# SA612Mixer_Simple.net
KiCad netlist of a schematic drawn in EAGLE
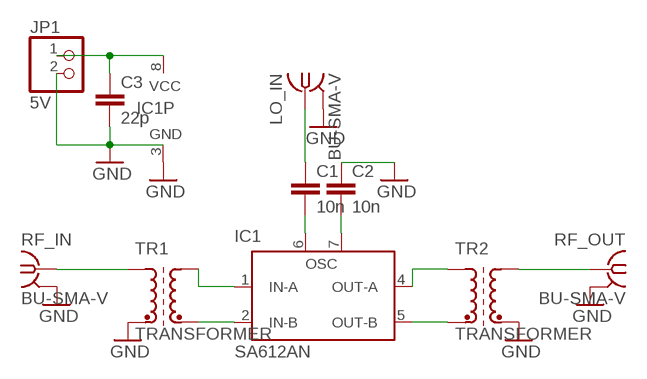
[diagram p0: schematic, sheet 1]

(export (version "E")
  (design (tool "Eeschema 10.0.6"))
  (components
    (comp (ref "C1")
      (value "10n")
      (footprint "eagle-import:C5B2.5")
      (libsource (lib "eagle-import") (part "C5/2.5"))
    )
    (comp (ref "C2")
      (value "10n")
      (footprint "eagle-import:C5B2.5")
      (libsource (lib "eagle-import") (part "C5/2.5"))
    )
    (comp (ref "C3")
      (value "22p")
      (footprint "eagle-import:C5B2.5")
      (libsource (lib "eagle-import") (part "C5/2.5"))
    )
    (comp (ref "IC1")
      (value "SA612AN")
      (footprint "eagle-import:DIL08")
      (libsource (lib "eagle-import") (part "SA612AN"))
    )
    (comp (ref "JP1")
      (value "5V")
      (footprint "eagle-import:1X02")
      (libsource (lib "eagle-import") (part "PINHD-1X2"))
    )
    (comp (ref "LO_IN")
      (value "BU-SMA-V")
      (footprint "eagle-import:BU-SMA-V")
      (libsource (lib "eagle-import") (part "BU-SMA-V"))
    )
    (comp (ref "RF_IN")
      (value "BU-SMA-V")
      (footprint "eagle-import:BU-SMA-V")
      (libsource (lib "eagle-import") (part "BU-SMA-V"))
    )
    (comp (ref "RF_OUT")
      (value "BU-SMA-V")
      (footprint "eagle-import:BU-SMA-V")
      (libsource (lib "eagle-import") (part "BU-SMA-V"))
    )
    (comp (ref "TR1")
      (value "TRANSFORMER")
      (footprint "eagle-import:TRANSFORMER1")
      (libsource (lib "eagle-import") (part "TRANSFORMER"))
    )
    (comp (ref "TR2")
      (value "TRANSFORMER")
      (footprint "eagle-import:TRANSFORMER1")
      (libsource (lib "eagle-import") (part "TRANSFORMER"))
    )
  )
  (nets
    (net (code "1") (name "GND") (class "Default")
      (node (ref "C2") (pin "1") (pinfunction "1_1") (pintype "passive"))
      (node (ref "C3") (pin "2") (pinfunction "2_2") (pintype "passive"))
      (node (ref "IC1") (pin "3") (pinfunction "GND_3") (pintype "power_in"))
      (node (ref "JP1") (pin "2") (pinfunction "2_2") (pintype "passive"))
      (node (ref "LO_IN") (pin "2") (pinfunction "2_2") (pintype "passive"))
      (node (ref "LO_IN") (pin "3") (pinfunction "2_3") (pintype "passive"))
      (node (ref "LO_IN") (pin "4") (pinfunction "2_4") (pintype "passive"))
      (node (ref "LO_IN") (pin "5") (pinfunction "2_5") (pintype "passive"))
      (node (ref "RF_IN") (pin "2") (pinfunction "2_2") (pintype "passive"))
      (node (ref "RF_IN") (pin "3") (pinfunction "2_3") (pintype "passive"))
      (node (ref "RF_IN") (pin "4") (pinfunction "2_4") (pintype "passive"))
      (node (ref "RF_IN") (pin "5") (pinfunction "2_5") (pintype "passive"))
      (node (ref "RF_OUT") (pin "2") (pinfunction "2_2") (pintype "passive"))
      (node (ref "RF_OUT") (pin "3") (pinfunction "2_3") (pintype "passive"))
      (node (ref "RF_OUT") (pin "4") (pinfunction "2_4") (pintype "passive"))
      (node (ref "RF_OUT") (pin "5") (pinfunction "2_5") (pintype "passive"))
      (node (ref "TR1") (pin "P$2") (pinfunction "E1_P$2") (pintype "passive"))
      (node (ref "TR2") (pin "P$4") (pinfunction "E2_P$4") (pintype "passive"))
    )
    (net (code "2") (name "Net-(C1-Pad1)") (class "Default")
      (node (ref "C1") (pin "1") (pinfunction "1_1") (pintype "passive"))
      (node (ref "LO_IN") (pin "1") (pinfunction "1_1") (pintype "passive"))
    )
    (net (code "3") (name "Net-(IC1A-IN-A)") (class "Default")
      (node (ref "IC1") (pin "1") (pinfunction "IN-A_1") (pintype "input"))
      (node (ref "TR1") (pin "P$3") (pinfunction "A2_P$3") (pintype "passive"))
    )
    (net (code "4") (name "Net-(IC1A-IN-B)") (class "Default")
      (node (ref "IC1") (pin "2") (pinfunction "IN-B_2") (pintype "input"))
      (node (ref "TR1") (pin "P$4") (pinfunction "E2_P$4") (pintype "passive"))
    )
    (net (code "5") (name "Net-(IC1A-OSC')") (class "Default")
      (node (ref "C2") (pin "2") (pinfunction "2_2") (pintype "passive"))
      (node (ref "IC1") (pin "7") (pinfunction "OSC'_7") (pintype "passive"))
    )
    (net (code "6") (name "Net-(IC1A-OSC)") (class "Default")
      (node (ref "C1") (pin "2") (pinfunction "2_2") (pintype "passive"))
      (node (ref "IC1") (pin "6") (pinfunction "OSC_6") (pintype "passive"))
    )
    (net (code "7") (name "Net-(IC1A-OUT-A)") (class "Default")
      (node (ref "IC1") (pin "4") (pinfunction "OUT-A_4") (pintype "input"))
      (node (ref "TR2") (pin "P$1") (pinfunction "A1_P$1") (pintype "passive"))
    )
    (net (code "8") (name "Net-(IC1A-OUT-B)") (class "Default")
      (node (ref "IC1") (pin "5") (pinfunction "OUT-B_5") (pintype "input"))
      (node (ref "TR2") (pin "P$2") (pinfunction "E1_P$2") (pintype "passive"))
    )
    (net (code "9") (name "Net-(IC1B-VCC)") (class "Default")
      (node (ref "C3") (pin "1") (pinfunction "1_1") (pintype "passive"))
      (node (ref "IC1") (pin "8") (pinfunction "VCC_8") (pintype "power_in"))
      (node (ref "JP1") (pin "1") (pinfunction "1_1") (pintype "passive"))
    )
    (net (code "10") (name "Net-(TR1-A1)") (class "Default")
      (node (ref "RF_IN") (pin "1") (pinfunction "1_1") (pintype "passive"))
      (node (ref "TR1") (pin "P$1") (pinfunction "A1_P$1") (pintype "passive"))
    )
    (net (code "11") (name "Net-(TR2-A2)") (class "Default")
      (node (ref "RF_OUT") (pin "1") (pinfunction "1_1") (pintype "passive"))
      (node (ref "TR2") (pin "P$3") (pinfunction "A2_P$3") (pintype "passive"))
    )
  )
)
